# placa2caras_v4.net
KiCad netlist of a schematic drawn in EAGLE
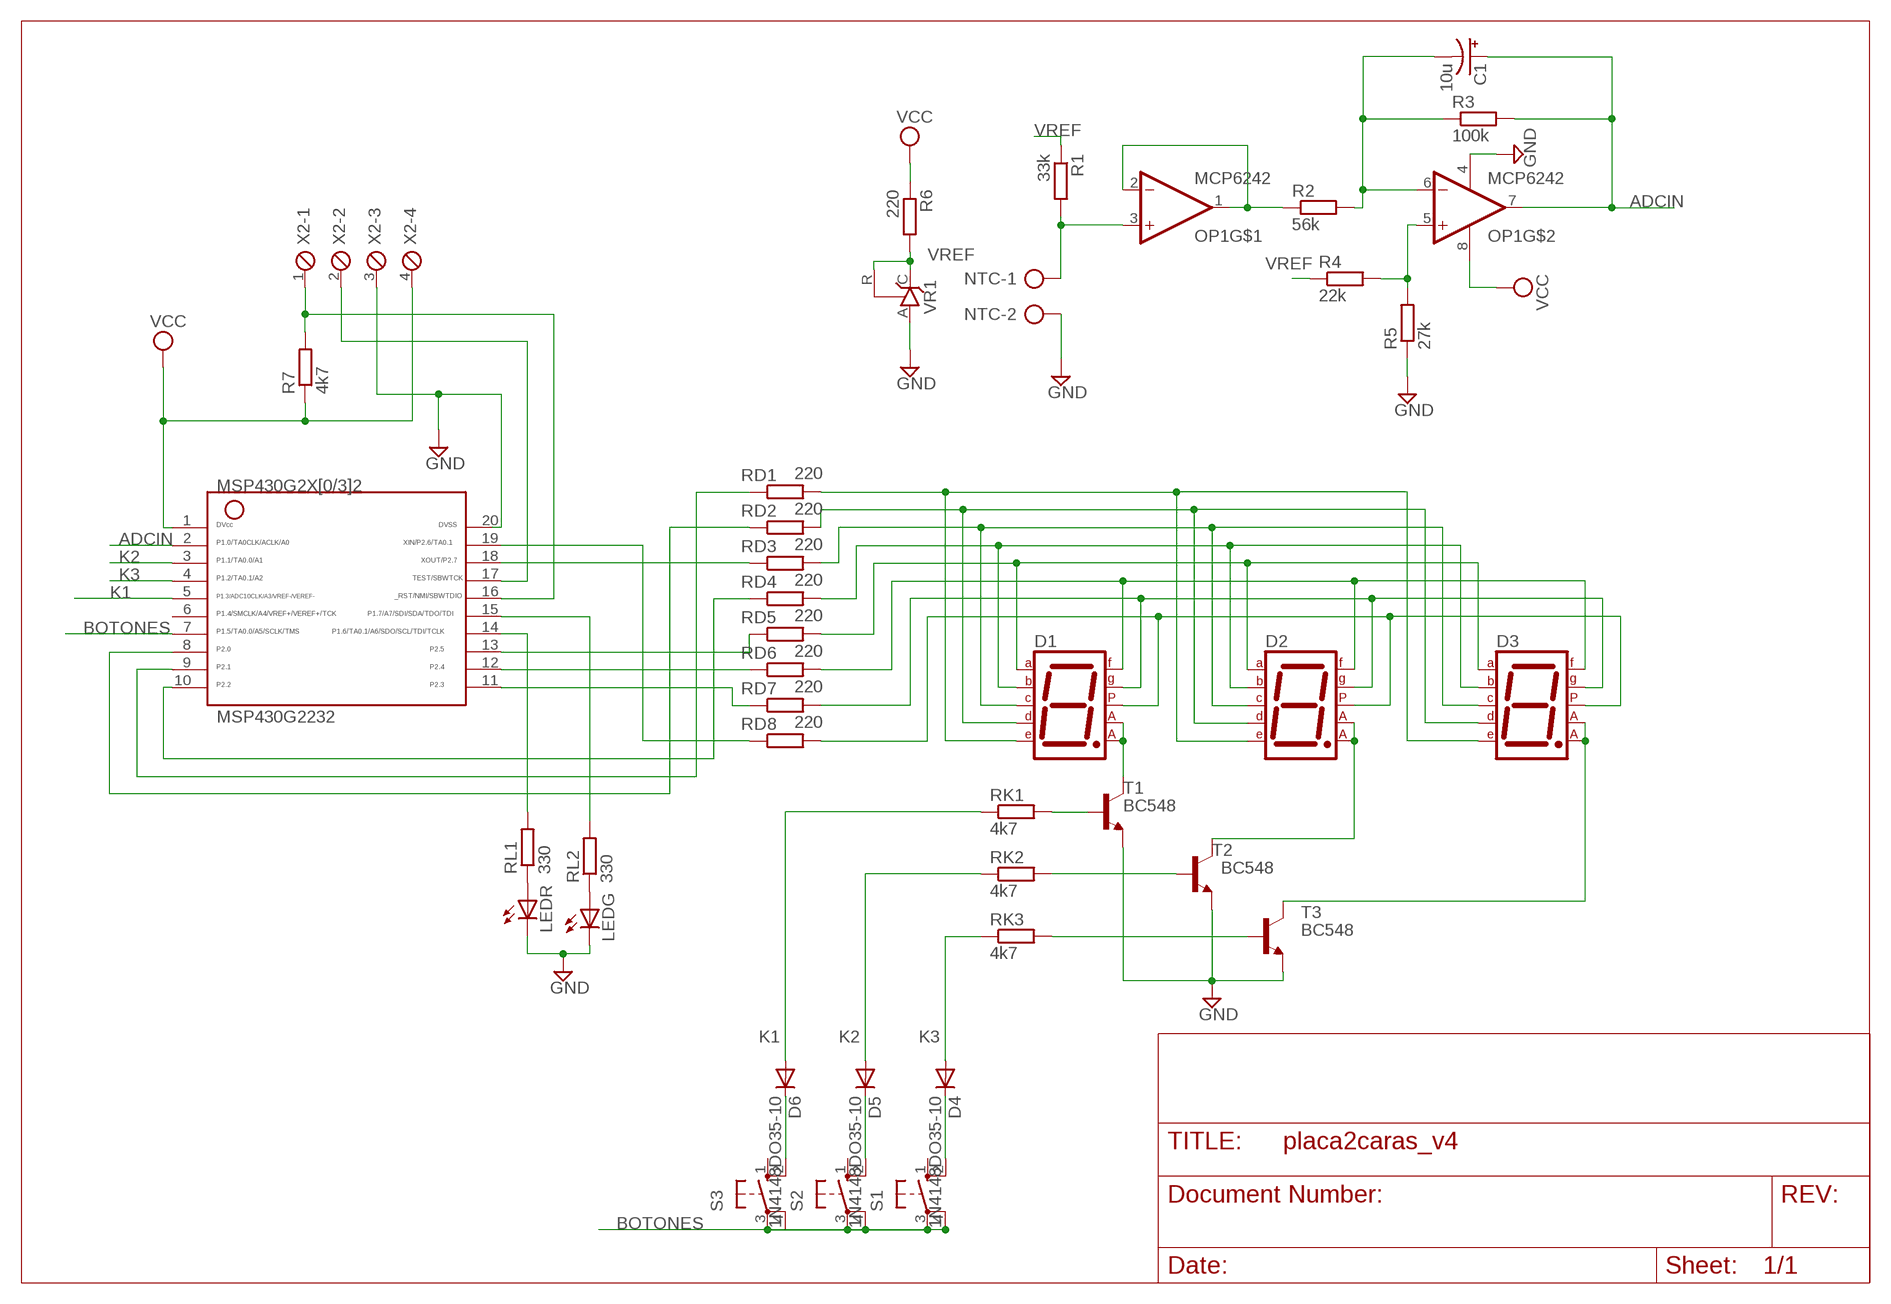
[diagram p0: schematic, sheet 1]

(export (version "E")
  (design (tool "Eeschema 10.0.6"))
  (components
    (comp (ref "C1")
      (value "10u")
      (footprint "eagle-import:E2,5-6E")
      (libsource (lib "eagle-import") (part "CPOL-USE2,5-6E"))
    )
    (comp (ref "D1")
      (value "7SEG-CA")
      (footprint "eagle-import:7SEG-13")
      (libsource (lib "eagle-import") (part "7SEG-CA"))
    )
    (comp (ref "D2")
      (value "7SEG-CA")
      (footprint "eagle-import:7SEG-13")
      (libsource (lib "eagle-import") (part "7SEG-CA"))
    )
    (comp (ref "D3")
      (value "7SEG-CA")
      (footprint "eagle-import:7SEG-13")
      (libsource (lib "eagle-import") (part "7SEG-CA"))
    )
    (comp (ref "D4")
      (value "1N4148DO35-10")
      (footprint "eagle-import:DO35-10")
      (libsource (lib "eagle-import") (part "1N4148DO35-10"))
    )
    (comp (ref "D5")
      (value "1N4148DO35-10")
      (footprint "eagle-import:DO35-10")
      (libsource (lib "eagle-import") (part "1N4148DO35-10"))
    )
    (comp (ref "D6")
      (value "1N4148DO35-10")
      (footprint "eagle-import:DO35-10")
      (libsource (lib "eagle-import") (part "1N4148DO35-10"))
    )
    (comp (ref "LEDG")
      (value "LED5MM")
      (footprint "eagle-import:LED5MM")
      (libsource (lib "eagle-import") (part "LED5MM"))
    )
    (comp (ref "LEDR")
      (value "LED5MM")
      (footprint "eagle-import:LED5MM")
      (libsource (lib "eagle-import") (part "LED5MM"))
    )
    (comp (ref "MSP430G2232")
      (value "G2X[0/3]2---N20")
      (footprint "eagle-import:N20")
      (libsource (lib "eagle-import") (part "G2X[0/3]2---N20"))
    )
    (comp (ref "NTC")
      (value "AK500/2")
      (footprint "eagle-import:AK500_2")
      (libsource (lib "eagle-import") (part "AK500/2"))
    )
    (comp (ref "OP1")
      (value "MCP6242")
      (footprint "eagle-import:DIL8_MOD")
      (libsource (lib "eagle-import") (part "MCP6242CONPADGORDO"))
    )
    (comp (ref "R1")
      (value "33k")
      (footprint "eagle-import:0207_10")
      (libsource (lib "eagle-import") (part "R-EU_0207/10"))
    )
    (comp (ref "R2")
      (value "56k")
      (footprint "eagle-import:0207_10")
      (libsource (lib "eagle-import") (part "R-EU_0207/10"))
    )
    (comp (ref "R3")
      (value "100k")
      (footprint "eagle-import:0207_10")
      (libsource (lib "eagle-import") (part "R-EU_0207/10"))
    )
    (comp (ref "R4")
      (value "22k")
      (footprint "eagle-import:0207_10")
      (libsource (lib "eagle-import") (part "R-EU_0207/10"))
    )
    (comp (ref "R5")
      (value "27k")
      (footprint "eagle-import:0207_10")
      (libsource (lib "eagle-import") (part "R-EU_0207/10"))
    )
    (comp (ref "R6")
      (value "220")
      (footprint "eagle-import:0207_10")
      (libsource (lib "eagle-import") (part "R-EU_0207/10"))
    )
    (comp (ref "R7")
      (value "4k7")
      (footprint "eagle-import:0207_10")
      (libsource (lib "eagle-import") (part "R-EU_0207/10"))
    )
    (comp (ref "RD1")
      (value "220")
      (footprint "eagle-import:0207_10")
      (libsource (lib "eagle-import") (part "R-EU_0207/10"))
    )
    (comp (ref "RD2")
      (value "220")
      (footprint "eagle-import:0207_10")
      (libsource (lib "eagle-import") (part "R-EU_0207/10"))
    )
    (comp (ref "RD3")
      (value "220")
      (footprint "eagle-import:0207_10")
      (libsource (lib "eagle-import") (part "R-EU_0207/10"))
    )
    (comp (ref "RD4")
      (value "220")
      (footprint "eagle-import:0207_10")
      (libsource (lib "eagle-import") (part "R-EU_0207/10"))
    )
    (comp (ref "RD5")
      (value "220")
      (footprint "eagle-import:0207_10")
      (libsource (lib "eagle-import") (part "R-EU_0207/10"))
    )
    (comp (ref "RD6")
      (value "220")
      (footprint "eagle-import:0207_10")
      (libsource (lib "eagle-import") (part "R-EU_0207/10"))
    )
    (comp (ref "RD7")
      (value "220")
      (footprint "eagle-import:0207_10")
      (libsource (lib "eagle-import") (part "R-EU_0207/10"))
    )
    (comp (ref "RD8")
      (value "220")
      (footprint "eagle-import:0207_10")
      (libsource (lib "eagle-import") (part "R-EU_0207/10"))
    )
    (comp (ref "RK1")
      (value "4k7")
      (footprint "eagle-import:0207_10")
      (libsource (lib "eagle-import") (part "R-EU_0207/10"))
    )
    (comp (ref "RK2")
      (value "4k7")
      (footprint "eagle-import:0207_10")
      (libsource (lib "eagle-import") (part "R-EU_0207/10"))
    )
    (comp (ref "RK3")
      (value "4k7")
      (footprint "eagle-import:0207_10")
      (libsource (lib "eagle-import") (part "R-EU_0207/10"))
    )
    (comp (ref "RL1")
      (value "330")
      (footprint "eagle-import:0207_10")
      (libsource (lib "eagle-import") (part "R-EU_0207/10"))
    )
    (comp (ref "RL2")
      (value "330")
      (footprint "eagle-import:0207_10")
      (libsource (lib "eagle-import") (part "R-EU_0207/10"))
    )
    (comp (ref "S1")
      (value "10-XX")
      (footprint "eagle-import:B3F-10XX")
      (fields (field (name "MPN") "B3F-1000"))
      (libsource (lib "eagle-import") (part "10-XX"))
    )
    (comp (ref "S2")
      (value "10-XX")
      (footprint "eagle-import:B3F-10XX")
      (fields (field (name "MPN") "B3F-1000"))
      (libsource (lib "eagle-import") (part "10-XX"))
    )
    (comp (ref "S3")
      (value "10-XX")
      (footprint "eagle-import:B3F-10XX")
      (fields (field (name "MPN") "B3F-1000"))
      (libsource (lib "eagle-import") (part "10-XX"))
    )
    (comp (ref "T1")
      (value "BC548")
      (footprint "eagle-import:TO92-EBC")
      (libsource (lib "eagle-import") (part "BC548"))
    )
    (comp (ref "T2")
      (value "BC548")
      (footprint "eagle-import:TO92-EBC")
      (libsource (lib "eagle-import") (part "BC548"))
    )
    (comp (ref "T3")
      (value "BC548")
      (footprint "eagle-import:TO92-EBC")
      (libsource (lib "eagle-import") (part "BC548"))
    )
    (comp (ref "VR1")
      (value "TL431CLP")
      (footprint "eagle-import:TO92-CLP")
      (libsource (lib "eagle-import") (part "TL431CLP"))
    )
    (comp (ref "X2")
      (value "MPT4")
      (footprint "eagle-import:4POL254")
      (libsource (lib "eagle-import") (part "MPT4"))
    )
  )
  (nets
    (net (code "1") (name "/ADCIN") (class "Default")
      (node (ref "C1") (pin "+") (pinfunction "+_+") (pintype "passive"))
      (node (ref "MSP430G2232") (pin "2") (pinfunction "2_2") (pintype "bidirectional"))
      (node (ref "OP1") (pin "7") (pinfunction "OUT_7") (pintype "output"))
      (node (ref "R3") (pin "2") (pinfunction "2_2") (pintype "passive"))
    )
    (net (code "2") (name "/BOTONES") (class "Default")
      (node (ref "MSP430G2232") (pin "7") (pinfunction "7_7") (pintype "bidirectional"))
      (node (ref "S1") (pin "3") (pinfunction "P_3") (pintype "passive"))
      (node (ref "S1") (pin "4") (pinfunction "P1_4") (pintype "passive"))
      (node (ref "S2") (pin "3") (pinfunction "P_3") (pintype "passive"))
      (node (ref "S2") (pin "4") (pinfunction "P1_4") (pintype "passive"))
      (node (ref "S3") (pin "3") (pinfunction "P_3") (pintype "passive"))
      (node (ref "S3") (pin "4") (pinfunction "P1_4") (pintype "passive"))
    )
    (net (code "3") (name "/K1") (class "Default")
      (node (ref "D6") (pin "A") (pinfunction "A_A") (pintype "passive"))
      (node (ref "MSP430G2232") (pin "5") (pinfunction "5_5") (pintype "bidirectional"))
      (node (ref "RK1") (pin "1") (pinfunction "1_1") (pintype "passive"))
    )
    (net (code "4") (name "/K2") (class "Default")
      (node (ref "D5") (pin "A") (pinfunction "A_A") (pintype "passive"))
      (node (ref "MSP430G2232") (pin "3") (pinfunction "3_3") (pintype "bidirectional"))
      (node (ref "RK2") (pin "1") (pinfunction "1_1") (pintype "passive"))
    )
    (net (code "5") (name "/K3") (class "Default")
      (node (ref "D4") (pin "A") (pinfunction "A_A") (pintype "passive"))
      (node (ref "MSP430G2232") (pin "4") (pinfunction "4_4") (pintype "bidirectional"))
      (node (ref "RK3") (pin "1") (pinfunction "1_1") (pintype "passive"))
    )
    (net (code "6") (name "/VREF") (class "Default")
      (node (ref "R1") (pin "1") (pinfunction "1_1") (pintype "passive"))
      (node (ref "R4") (pin "1") (pinfunction "1_1") (pintype "passive"))
      (node (ref "R6") (pin "2") (pinfunction "2_2") (pintype "passive"))
      (node (ref "VR1") (pin "C") (pinfunction "C_C") (pintype "passive"))
      (node (ref "VR1") (pin "R") (pinfunction "R_R") (pintype "passive"))
    )
    (net (code "7") (name "GND") (class "Default")
      (node (ref "LEDG") (pin "K") (pinfunction "C_K") (pintype "passive"))
      (node (ref "LEDR") (pin "K") (pinfunction "C_K") (pintype "passive"))
      (node (ref "MSP430G2232") (pin "20") (pinfunction "20_20") (pintype "bidirectional"))
      (node (ref "NTC") (pin "2") (pinfunction "KL_2") (pintype "passive"))
      (node (ref "OP1") (pin "4") (pinfunction "V-_4") (pintype "power_in"))
      (node (ref "R5") (pin "1") (pinfunction "1_1") (pintype "passive"))
      (node (ref "T1") (pin "E") (pinfunction "E_E") (pintype "passive"))
      (node (ref "T2") (pin "E") (pinfunction "E_E") (pintype "passive"))
      (node (ref "T3") (pin "E") (pinfunction "E_E") (pintype "passive"))
      (node (ref "VR1") (pin "A") (pinfunction "A_A") (pintype "passive"))
      (node (ref "X2") (pin "3") (pinfunction "1_3") (pintype "passive"))
    )
    (net (code "8") (name "Net-(D1-A)") (class "Default")
      (node (ref "D1") (pin "7") (pinfunction "A_7") (pintype "passive"))
      (node (ref "D2") (pin "7") (pinfunction "A_7") (pintype "passive"))
      (node (ref "D3") (pin "7") (pinfunction "A_7") (pintype "passive"))
      (node (ref "RD5") (pin "2") (pinfunction "2_2") (pintype "passive"))
    )
    (net (code "9") (name "Net-(D1-B)") (class "Default")
      (node (ref "D1") (pin "6") (pinfunction "B_6") (pintype "passive"))
      (node (ref "D2") (pin "6") (pinfunction "B_6") (pintype "passive"))
      (node (ref "D3") (pin "6") (pinfunction "B_6") (pintype "passive"))
      (node (ref "RD4") (pin "2") (pinfunction "2_2") (pintype "passive"))
    )
    (net (code "10") (name "Net-(D1-C)") (class "Default")
      (node (ref "D1") (pin "4") (pinfunction "C_4") (pintype "passive"))
      (node (ref "D2") (pin "4") (pinfunction "C_4") (pintype "passive"))
      (node (ref "D3") (pin "4") (pinfunction "C_4") (pintype "passive"))
      (node (ref "RD3") (pin "2") (pinfunction "2_2") (pintype "passive"))
    )
    (net (code "11") (name "Net-(D1-CA1)") (class "Default")
      (node (ref "D1") (pin "3") (pinfunction "CA1_3") (pintype "passive"))
      (node (ref "D1") (pin "8") (pinfunction "CA2_8") (pintype "passive"))
      (node (ref "T1") (pin "C") (pinfunction "C_C") (pintype "passive"))
    )
    (net (code "12") (name "Net-(D1-D)") (class "Default")
      (node (ref "D1") (pin "2") (pinfunction "D_2") (pintype "passive"))
      (node (ref "D2") (pin "2") (pinfunction "D_2") (pintype "passive"))
      (node (ref "D3") (pin "2") (pinfunction "D_2") (pintype "passive"))
      (node (ref "RD2") (pin "2") (pinfunction "2_2") (pintype "passive"))
    )
    (net (code "13") (name "Net-(D1-DP)") (class "Default")
      (node (ref "D1") (pin "5") (pinfunction "DP_5") (pintype "passive"))
      (node (ref "D2") (pin "5") (pinfunction "DP_5") (pintype "passive"))
      (node (ref "D3") (pin "5") (pinfunction "DP_5") (pintype "passive"))
      (node (ref "RD8") (pin "2") (pinfunction "2_2") (pintype "passive"))
    )
    (net (code "14") (name "Net-(D1-E)") (class "Default")
      (node (ref "D1") (pin "1") (pinfunction "E_1") (pintype "passive"))
      (node (ref "D2") (pin "1") (pinfunction "E_1") (pintype "passive"))
      (node (ref "D3") (pin "1") (pinfunction "E_1") (pintype "passive"))
      (node (ref "RD1") (pin "2") (pinfunction "2_2") (pintype "passive"))
    )
    (net (code "15") (name "Net-(D1-F)") (class "Default")
      (node (ref "D1") (pin "9") (pinfunction "F_9") (pintype "passive"))
      (node (ref "D2") (pin "9") (pinfunction "F_9") (pintype "passive"))
      (node (ref "D3") (pin "9") (pinfunction "F_9") (pintype "passive"))
      (node (ref "RD6") (pin "2") (pinfunction "2_2") (pintype "passive"))
    )
    (net (code "16") (name "Net-(D1-G)") (class "Default")
      (node (ref "D1") (pin "10") (pinfunction "G_10") (pintype "passive"))
      (node (ref "D2") (pin "10") (pinfunction "G_10") (pintype "passive"))
      (node (ref "D3") (pin "10") (pinfunction "G_10") (pintype "passive"))
      (node (ref "RD7") (pin "2") (pinfunction "2_2") (pintype "passive"))
    )
    (net (code "17") (name "Net-(D2-CA1)") (class "Default")
      (node (ref "D2") (pin "3") (pinfunction "CA1_3") (pintype "passive"))
      (node (ref "D2") (pin "8") (pinfunction "CA2_8") (pintype "passive"))
      (node (ref "T2") (pin "C") (pinfunction "C_C") (pintype "passive"))
    )
    (net (code "18") (name "Net-(D3-CA1)") (class "Default")
      (node (ref "D3") (pin "3") (pinfunction "CA1_3") (pintype "passive"))
      (node (ref "D3") (pin "8") (pinfunction "CA2_8") (pintype "passive"))
      (node (ref "T3") (pin "C") (pinfunction "C_C") (pintype "passive"))
    )
    (net (code "19") (name "Net-(LEDG-PadA)") (class "Default")
      (node (ref "LEDG") (pin "A") (pinfunction "A_A") (pintype "passive"))
      (node (ref "RL2") (pin "1") (pinfunction "1_1") (pintype "passive"))
    )
    (net (code "20") (name "Net-(LEDR-PadA)") (class "Default")
      (node (ref "LEDR") (pin "A") (pinfunction "A_A") (pintype "passive"))
      (node (ref "RL1") (pin "1") (pinfunction "1_1") (pintype "passive"))
    )
    (net (code "21") (name "Net-(MSP430G2232-Pad8)") (class "Default")
      (node (ref "MSP430G2232") (pin "8") (pinfunction "8_8") (pintype "bidirectional"))
      (node (ref "RD2") (pin "1") (pinfunction "1_1") (pintype "passive"))
    )
    (net (code "22") (name "Net-(MSP430G2232-Pad9)") (class "Default")
      (node (ref "MSP430G2232") (pin "9") (pinfunction "9_9") (pintype "bidirectional"))
      (node (ref "RD1") (pin "1") (pinfunction "1_1") (pintype "passive"))
    )
    (net (code "23") (name "Net-(MSP430G2232-Pad10)") (class "Default")
      (node (ref "MSP430G2232") (pin "10") (pinfunction "10_10") (pintype "bidirectional"))
      (node (ref "RD4") (pin "1") (pinfunction "1_1") (pintype "passive"))
    )
    (net (code "24") (name "Net-(MSP430G2232-Pad11)") (class "Default")
      (node (ref "MSP430G2232") (pin "11") (pinfunction "11_11") (pintype "bidirectional"))
      (node (ref "RD7") (pin "1") (pinfunction "1_1") (pintype "passive"))
    )
    (net (code "25") (name "Net-(MSP430G2232-Pad12)") (class "Default")
      (node (ref "MSP430G2232") (pin "12") (pinfunction "12_12") (pintype "bidirectional"))
      (node (ref "RD6") (pin "1") (pinfunction "1_1") (pintype "passive"))
    )
    (net (code "26") (name "Net-(MSP430G2232-Pad13)") (class "Default")
      (node (ref "MSP430G2232") (pin "13") (pinfunction "13_13") (pintype "bidirectional"))
      (node (ref "RD5") (pin "1") (pinfunction "1_1") (pintype "passive"))
    )
    (net (code "27") (name "Net-(MSP430G2232-Pad14)") (class "Default")
      (node (ref "MSP430G2232") (pin "14") (pinfunction "14_14") (pintype "bidirectional"))
      (node (ref "RL1") (pin "2") (pinfunction "2_2") (pintype "passive"))
    )
    (net (code "28") (name "Net-(MSP430G2232-Pad15)") (class "Default")
      (node (ref "MSP430G2232") (pin "15") (pinfunction "15_15") (pintype "bidirectional"))
      (node (ref "RL2") (pin "2") (pinfunction "2_2") (pintype "passive"))
    )
    (net (code "29") (name "Net-(MSP430G2232-Pad16)") (class "Default")
      (node (ref "MSP430G2232") (pin "16") (pinfunction "16_16") (pintype "bidirectional"))
      (node (ref "R7") (pin "2") (pinfunction "2_2") (pintype "passive"))
      (node (ref "X2") (pin "1") (pinfunction "1_1") (pintype "passive"))
    )
    (net (code "30") (name "Net-(MSP430G2232-Pad18)") (class "Default")
      (node (ref "MSP430G2232") (pin "18") (pinfunction "18_18") (pintype "bidirectional"))
      (node (ref "RD3") (pin "1") (pinfunction "1_1") (pintype "passive"))
    )
    (net (code "31") (name "Net-(MSP430G2232-Pad19)") (class "Default")
      (node (ref "MSP430G2232") (pin "19") (pinfunction "19_19") (pintype "bidirectional"))
      (node (ref "RD8") (pin "1") (pinfunction "1_1") (pintype "passive"))
    )
    (net (code "32") (name "Net-(NTCA-KL)") (class "Default")
      (node (ref "NTC") (pin "1") (pinfunction "KL_1") (pintype "passive"))
      (node (ref "OP1") (pin "3") (pinfunction "+IN_3") (pintype "input"))
      (node (ref "R1") (pin "2") (pinfunction "2_2") (pintype "passive"))
    )
    (net (code "33") (name "Net-(OP1A--IN)") (class "Default")
      (node (ref "OP1") (pin "1") (pinfunction "OUT_1") (pintype "output"))
      (node (ref "OP1") (pin "2") (pinfunction "-IN_2") (pintype "input"))
      (node (ref "R2") (pin "1") (pinfunction "1_1") (pintype "passive"))
    )
    (net (code "34") (name "Net-(OP1B-+IN)") (class "Default")
      (node (ref "OP1") (pin "5") (pinfunction "+IN_5") (pintype "input"))
      (node (ref "R4") (pin "2") (pinfunction "2_2") (pintype "passive"))
      (node (ref "R5") (pin "2") (pinfunction "2_2") (pintype "passive"))
    )
    (net (code "35") (name "Net-(OP1B--IN)") (class "Default")
      (node (ref "C1") (pin "-") (pinfunction "-_-") (pintype "passive"))
      (node (ref "OP1") (pin "6") (pinfunction "-IN_6") (pintype "input"))
      (node (ref "R2") (pin "2") (pinfunction "2_2") (pintype "passive"))
      (node (ref "R3") (pin "1") (pinfunction "1_1") (pintype "passive"))
    )
    (net (code "36") (name "Net-(RK1-Pad2)") (class "Default")
      (node (ref "RK1") (pin "2") (pinfunction "2_2") (pintype "passive"))
      (node (ref "T1") (pin "B") (pinfunction "B_B") (pintype "passive"))
    )
    (net (code "37") (name "Net-(RK2-Pad2)") (class "Default")
      (node (ref "RK2") (pin "2") (pinfunction "2_2") (pintype "passive"))
      (node (ref "T2") (pin "B") (pinfunction "B_B") (pintype "passive"))
    )
    (net (code "38") (name "Net-(RK3-Pad2)") (class "Default")
      (node (ref "RK3") (pin "2") (pinfunction "2_2") (pintype "passive"))
      (node (ref "T3") (pin "B") (pinfunction "B_B") (pintype "passive"))
    )
    (net (code "39") (name "Net-(S1-S1)") (class "Default")
      (node (ref "D4") (pin "C") (pinfunction "C_C") (pintype "passive"))
      (node (ref "S1") (pin "2") (pinfunction "S1_2") (pintype "passive"))
    )
    (net (code "40") (name "Net-(S2-S1)") (class "Default")
      (node (ref "D5") (pin "C") (pinfunction "C_C") (pintype "passive"))
      (node (ref "S2") (pin "2") (pinfunction "S1_2") (pintype "passive"))
    )
    (net (code "41") (name "Net-(S3-S1)") (class "Default")
      (node (ref "D6") (pin "C") (pinfunction "C_C") (pintype "passive"))
      (node (ref "S3") (pin "2") (pinfunction "S1_2") (pintype "passive"))
    )
    (net (code "42") (name "Net-(X2B-1)") (class "Default")
      (node (ref "MSP430G2232") (pin "17") (pinfunction "17_17") (pintype "bidirectional"))
      (node (ref "X2") (pin "2") (pinfunction "1_2") (pintype "passive"))
    )
    (net (code "43") (name "VCC") (class "Default")
      (node (ref "MSP430G2232") (pin "1") (pinfunction "1_1") (pintype "bidirectional"))
      (node (ref "OP1") (pin "8") (pinfunction "V+_8") (pintype "power_in"))
      (node (ref "R6") (pin "1") (pinfunction "1_1") (pintype "passive"))
      (node (ref "R7") (pin "1") (pinfunction "1_1") (pintype "passive"))
      (node (ref "X2") (pin "4") (pinfunction "1_4") (pintype "passive"))
    )
    (net (code "44") (name "unconnected-(MSP430G2232-Pad6)") (class "Default")
      (node (ref "MSP430G2232") (pin "6") (pinfunction "6_6") (pintype "bidirectional"))
    )
    (net (code "45") (name "unconnected-(S1-S-Pad1)") (class "Default")
      (node (ref "S1") (pin "1") (pinfunction "S_1") (pintype "passive"))
    )
    (net (code "46") (name "unconnected-(S2-S-Pad1)") (class "Default")
      (node (ref "S2") (pin "1") (pinfunction "S_1") (pintype "passive"))
    )
    (net (code "47") (name "unconnected-(S3-S-Pad1)") (class "Default")
      (node (ref "S3") (pin "1") (pinfunction "S_1") (pintype "passive"))
    )
  )
)
